# Main_DMB-4773.net
KiCad netlist of a schematic drawn in EAGLE
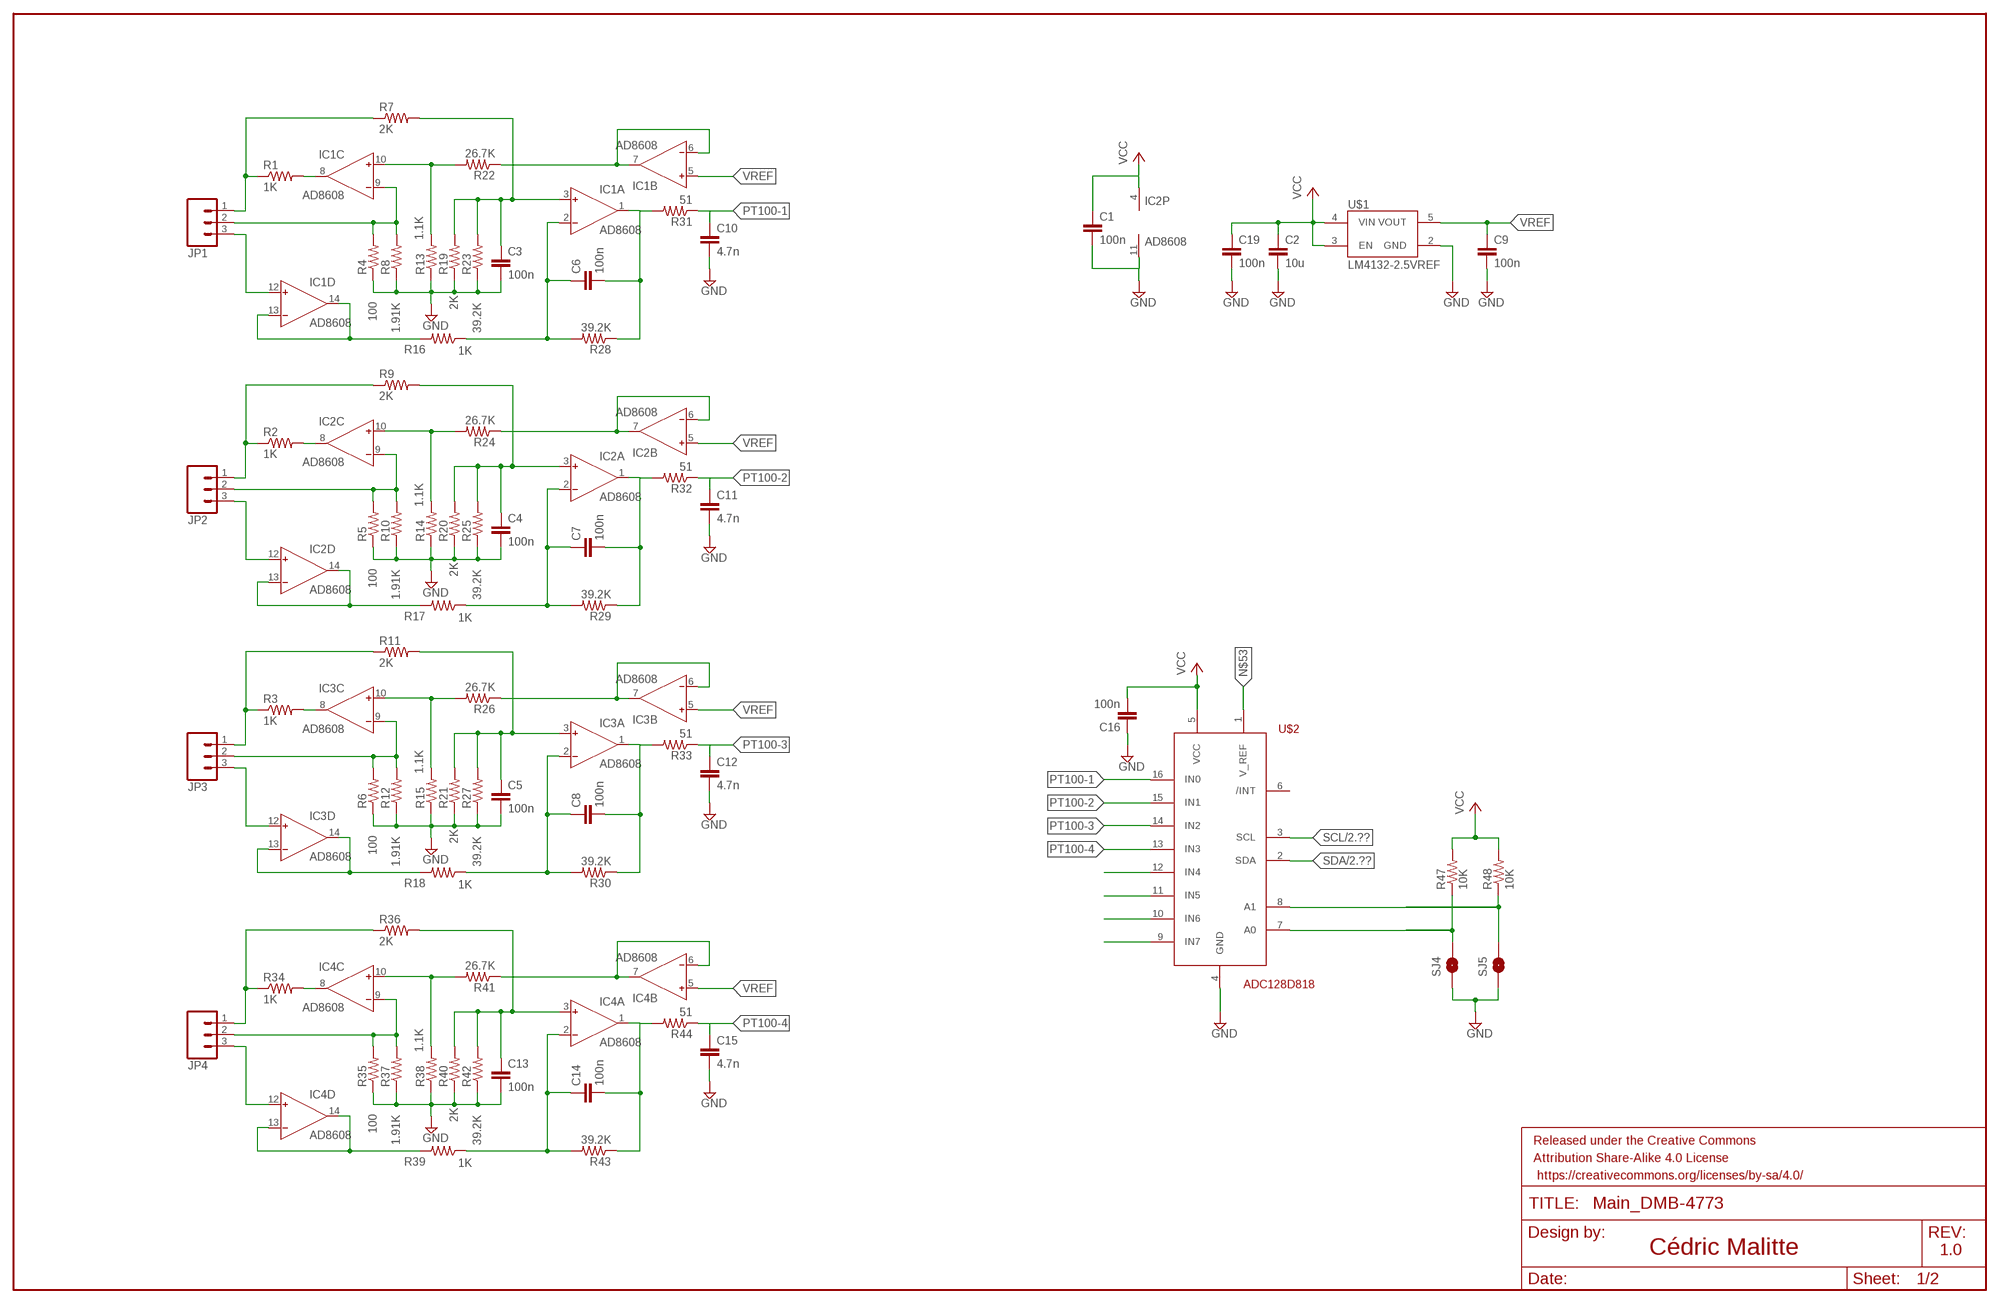
[diagram p0: schematic, sheet 1]
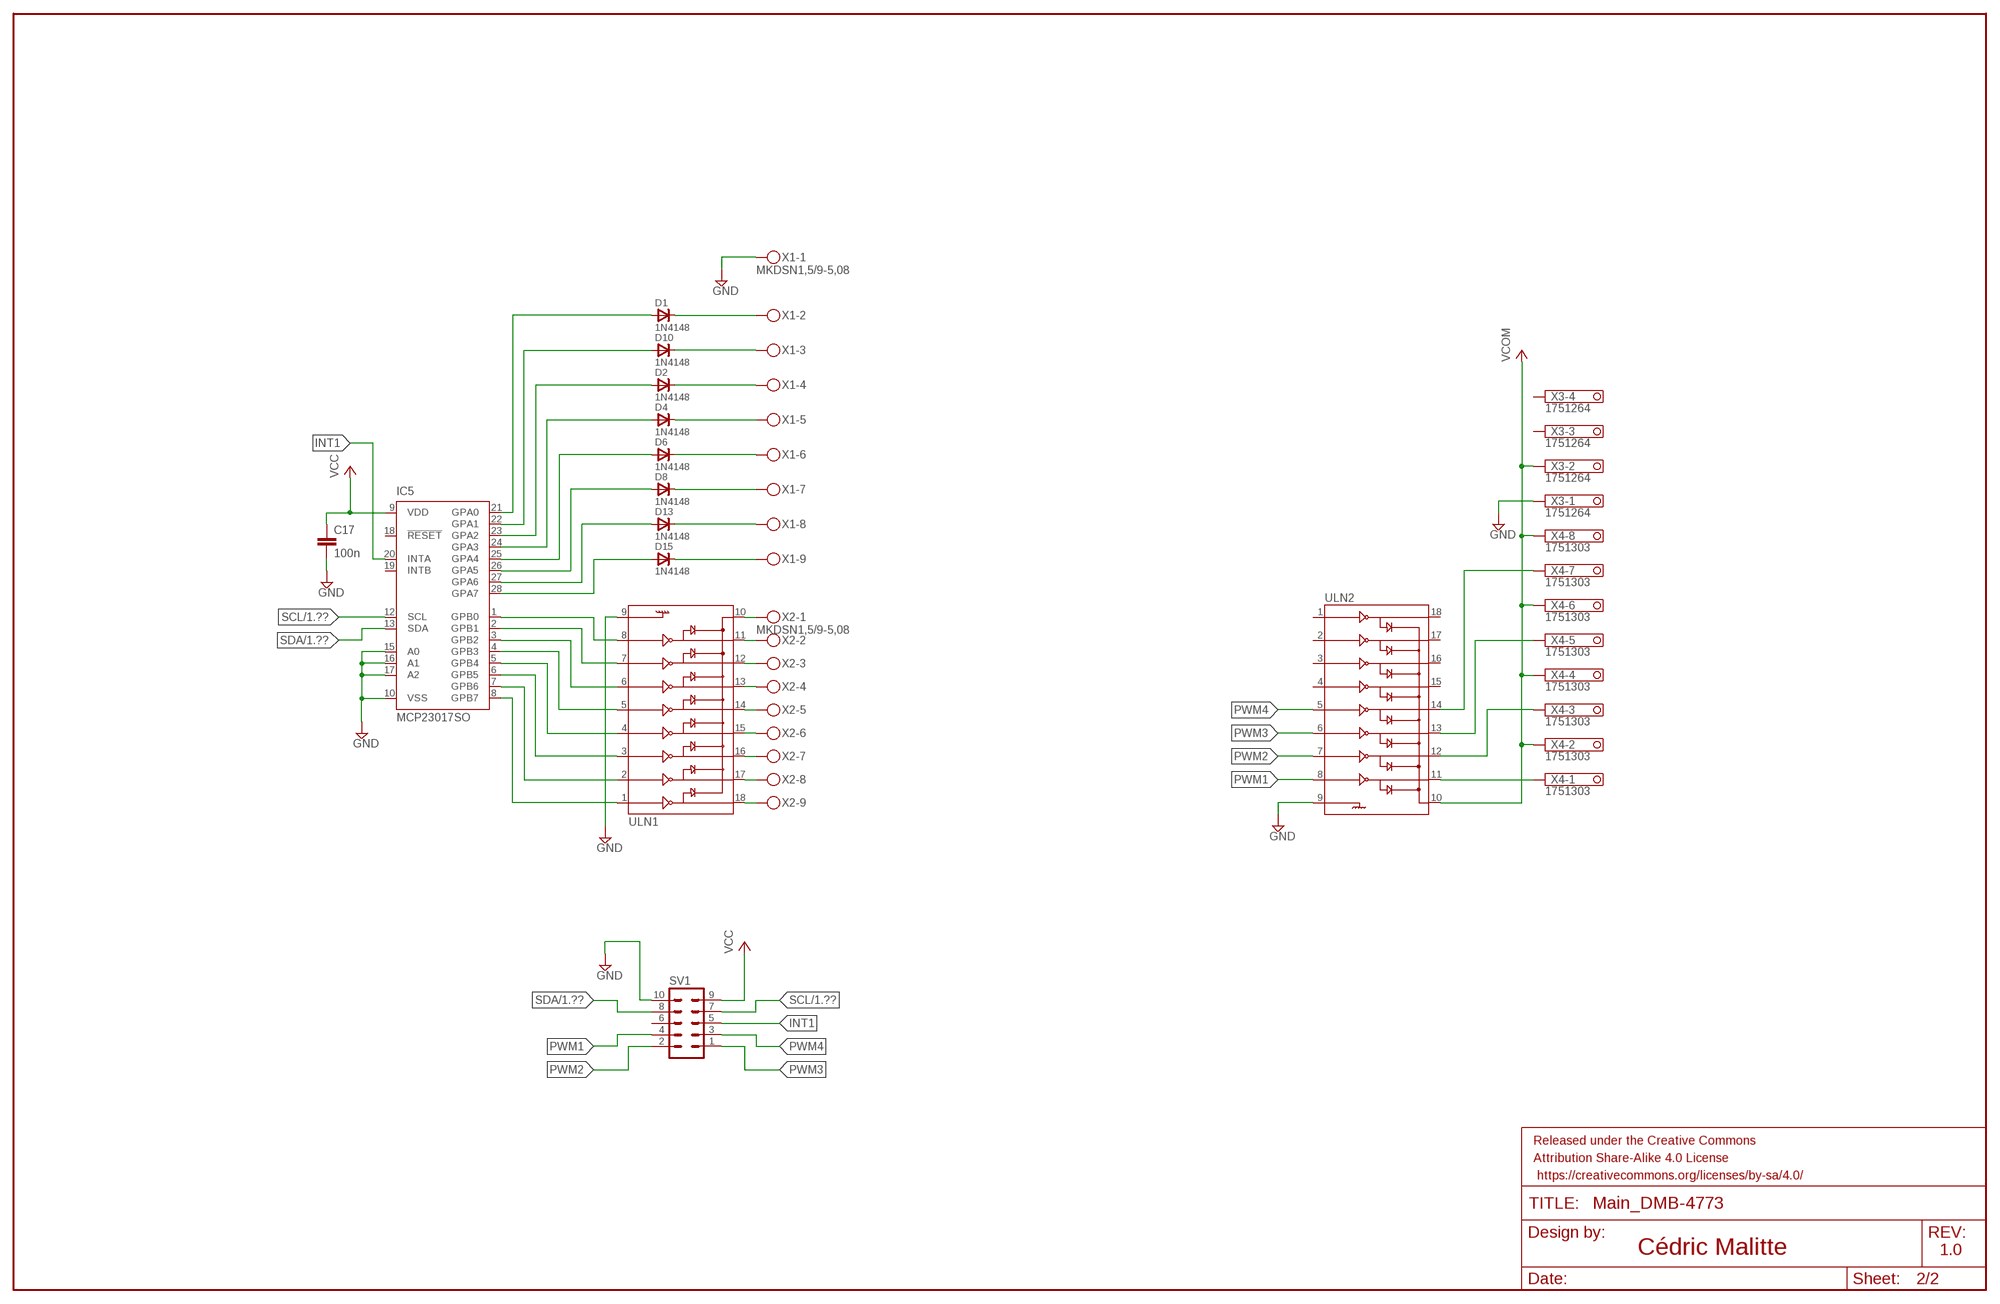
[diagram p1: schematic, sheet 2]

(export (version "E")
  (design (tool "Eeschema 10.0.6"))
  (components
    (comp (ref "C1")
      (value "100n")
      (footprint "eagle-import:0805")
      (libsource (lib "eagle-import") (part "CAP0805"))
    )
    (comp (ref "C2")
      (value "10u")
      (footprint "eagle-import:0805")
      (libsource (lib "eagle-import") (part "CAP0805"))
    )
    (comp (ref "C3")
      (value "100n")
      (footprint "eagle-import:0805")
      (libsource (lib "eagle-import") (part "CAP0805"))
    )
    (comp (ref "C4")
      (value "100n")
      (footprint "eagle-import:0805")
      (libsource (lib "eagle-import") (part "CAP0805"))
    )
    (comp (ref "C5")
      (value "100n")
      (footprint "eagle-import:0805")
      (libsource (lib "eagle-import") (part "CAP0805"))
    )
    (comp (ref "C6")
      (value "100n")
      (footprint "eagle-import:0805")
      (libsource (lib "eagle-import") (part "CAP0805"))
    )
    (comp (ref "C7")
      (value "100n")
      (footprint "eagle-import:0805")
      (libsource (lib "eagle-import") (part "CAP0805"))
    )
    (comp (ref "C8")
      (value "100n")
      (footprint "eagle-import:0805")
      (libsource (lib "eagle-import") (part "CAP0805"))
    )
    (comp (ref "C9")
      (value "100n")
      (footprint "eagle-import:0805")
      (libsource (lib "eagle-import") (part "CAP0805"))
    )
    (comp (ref "C10")
      (value "4.7n")
      (footprint "eagle-import:0805")
      (libsource (lib "eagle-import") (part "CAP0805"))
    )
    (comp (ref "C11")
      (value "4.7n")
      (footprint "eagle-import:0805")
      (libsource (lib "eagle-import") (part "CAP0805"))
    )
    (comp (ref "C12")
      (value "4.7n")
      (footprint "eagle-import:0805")
      (libsource (lib "eagle-import") (part "CAP0805"))
    )
    (comp (ref "C13")
      (value "100n")
      (footprint "eagle-import:0805")
      (libsource (lib "eagle-import") (part "CAP0805"))
    )
    (comp (ref "C14")
      (value "100n")
      (footprint "eagle-import:0805")
      (libsource (lib "eagle-import") (part "CAP0805"))
    )
    (comp (ref "C15")
      (value "4.7n")
      (footprint "eagle-import:0805")
      (libsource (lib "eagle-import") (part "CAP0805"))
    )
    (comp (ref "C16")
      (value "100n")
      (footprint "eagle-import:0805")
      (libsource (lib "eagle-import") (part "CAP0805"))
    )
    (comp (ref "C19")
      (value "100n")
      (footprint "eagle-import:0805")
      (libsource (lib "eagle-import") (part "CAP0805"))
    )
    (comp (ref "FRAME1")
      (value "FRAME-LEDGER")
      (footprint "eagle-import:CREATIVE_COMMONS")
      (libsource (lib "eagle-import") (part "FRAME-LEDGER"))
    )
    (comp (ref "IC1")
      (value "AD8608")
      (footprint "eagle-import:SO14")
      (fields (field (name "MPN") "AD8609ARZ"))
      (libsource (lib "eagle-import") (part "AD8609R"))
    )
    (comp (ref "IC2")
      (value "AD8608")
      (footprint "eagle-import:SO14")
      (fields (field (name "MPN") "AD8609ARZ"))
      (libsource (lib "eagle-import") (part "AD8609R"))
    )
    (comp (ref "IC3")
      (value "AD8608")
      (footprint "eagle-import:SO14")
      (fields (field (name "MPN") "AD8609ARZ"))
      (libsource (lib "eagle-import") (part "AD8609R"))
    )
    (comp (ref "IC4")
      (value "AD8608")
      (footprint "eagle-import:SO14")
      (fields (field (name "MPN") "AD8609ARZ"))
      (libsource (lib "eagle-import") (part "AD8609R"))
    )
    (comp (ref "JP1")
      (value "M03SCREW")
      (footprint "eagle-import:SCREWTERMINAL-3.5MM-3")
      (libsource (lib "eagle-import") (part "M03SCREW"))
    )
    (comp (ref "JP2")
      (value "M03SCREW")
      (footprint "eagle-import:SCREWTERMINAL-3.5MM-3")
      (libsource (lib "eagle-import") (part "M03SCREW"))
    )
    (comp (ref "JP3")
      (value "M03SCREW")
      (footprint "eagle-import:SCREWTERMINAL-3.5MM-3")
      (libsource (lib "eagle-import") (part "M03SCREW"))
    )
    (comp (ref "JP4")
      (value "M03SCREW")
      (footprint "eagle-import:SCREWTERMINAL-3.5MM-3")
      (libsource (lib "eagle-import") (part "M03SCREW"))
    )
    (comp (ref "R1")
      (value "1K")
      (footprint "eagle-import:0805")
      (libsource (lib "eagle-import") (part "RESISTOR0805-RES"))
    )
    (comp (ref "R2")
      (value "1K")
      (footprint "eagle-import:0805")
      (libsource (lib "eagle-import") (part "RESISTOR0805-RES"))
    )
    (comp (ref "R3")
      (value "1K")
      (footprint "eagle-import:0805")
      (libsource (lib "eagle-import") (part "RESISTOR0805-RES"))
    )
    (comp (ref "R4")
      (value "100")
      (footprint "eagle-import:0805")
      (libsource (lib "eagle-import") (part "RESISTOR0805-RES"))
    )
    (comp (ref "R5")
      (value "100")
      (footprint "eagle-import:0805")
      (libsource (lib "eagle-import") (part "RESISTOR0805-RES"))
    )
    (comp (ref "R6")
      (value "100")
      (footprint "eagle-import:0805")
      (libsource (lib "eagle-import") (part "RESISTOR0805-RES"))
    )
    (comp (ref "R7")
      (value "2K")
      (footprint "eagle-import:0805")
      (libsource (lib "eagle-import") (part "RESISTOR0805-RES"))
    )
    (comp (ref "R8")
      (value "1.91K")
      (footprint "eagle-import:0805")
      (libsource (lib "eagle-import") (part "RESISTOR0805-RES"))
    )
    (comp (ref "R9")
      (value "2K")
      (footprint "eagle-import:0805")
      (libsource (lib "eagle-import") (part "RESISTOR0805-RES"))
    )
    (comp (ref "R10")
      (value "1.91K")
      (footprint "eagle-import:0805")
      (libsource (lib "eagle-import") (part "RESISTOR0805-RES"))
    )
    (comp (ref "R11")
      (value "2K")
      (footprint "eagle-import:0805")
      (libsource (lib "eagle-import") (part "RESISTOR0805-RES"))
    )
    (comp (ref "R12")
      (value "1.91K")
      (footprint "eagle-import:0805")
      (libsource (lib "eagle-import") (part "RESISTOR0805-RES"))
    )
    (comp (ref "R13")
      (value "1.1K")
      (footprint "eagle-import:0805")
      (libsource (lib "eagle-import") (part "RESISTOR0805-RES"))
    )
    (comp (ref "R14")
      (value "1.1K")
      (footprint "eagle-import:0805")
      (libsource (lib "eagle-import") (part "RESISTOR0805-RES"))
    )
    (comp (ref "R15")
      (value "1.1K")
      (footprint "eagle-import:0805")
      (libsource (lib "eagle-import") (part "RESISTOR0805-RES"))
    )
    (comp (ref "R16")
      (value "1K")
      (footprint "eagle-import:0805")
      (libsource (lib "eagle-import") (part "RESISTOR0805-RES"))
    )
    (comp (ref "R17")
      (value "1K")
      (footprint "eagle-import:0805")
      (libsource (lib "eagle-import") (part "RESISTOR0805-RES"))
    )
    (comp (ref "R18")
      (value "1K")
      (footprint "eagle-import:0805")
      (libsource (lib "eagle-import") (part "RESISTOR0805-RES"))
    )
    (comp (ref "R19")
      (value "2K")
      (footprint "eagle-import:0805")
      (libsource (lib "eagle-import") (part "RESISTOR0805-RES"))
    )
    (comp (ref "R20")
      (value "2K")
      (footprint "eagle-import:0805")
      (libsource (lib "eagle-import") (part "RESISTOR0805-RES"))
    )
    (comp (ref "R21")
      (value "2K")
      (footprint "eagle-import:0805")
      (libsource (lib "eagle-import") (part "RESISTOR0805-RES"))
    )
    (comp (ref "R22")
      (value "26.7K")
      (footprint "eagle-import:0805")
      (libsource (lib "eagle-import") (part "RESISTOR0805-RES"))
    )
    (comp (ref "R23")
      (value "39.2K")
      (footprint "eagle-import:0805")
      (libsource (lib "eagle-import") (part "RESISTOR0805-RES"))
    )
    (comp (ref "R24")
      (value "26.7K")
      (footprint "eagle-import:0805")
      (libsource (lib "eagle-import") (part "RESISTOR0805-RES"))
    )
    (comp (ref "R25")
      (value "39.2K")
      (footprint "eagle-import:0805")
      (libsource (lib "eagle-import") (part "RESISTOR0805-RES"))
    )
    (comp (ref "R26")
      (value "26.7K")
      (footprint "eagle-import:0805")
      (libsource (lib "eagle-import") (part "RESISTOR0805-RES"))
    )
    (comp (ref "R27")
      (value "39.2K")
      (footprint "eagle-import:0805")
      (libsource (lib "eagle-import") (part "RESISTOR0805-RES"))
    )
    (comp (ref "R28")
      (value "39.2K")
      (footprint "eagle-import:0805")
      (libsource (lib "eagle-import") (part "RESISTOR0805-RES"))
    )
    (comp (ref "R29")
      (value "39.2K")
      (footprint "eagle-import:0805")
      (libsource (lib "eagle-import") (part "RESISTOR0805-RES"))
    )
    (comp (ref "R30")
      (value "39.2K")
      (footprint "eagle-import:0805")
      (libsource (lib "eagle-import") (part "RESISTOR0805-RES"))
    )
    (comp (ref "R31")
      (value "51")
      (footprint "eagle-import:0805")
      (libsource (lib "eagle-import") (part "RESISTOR0805-RES"))
    )
    (comp (ref "R32")
      (value "51")
      (footprint "eagle-import:0805")
      (libsource (lib "eagle-import") (part "RESISTOR0805-RES"))
    )
    (comp (ref "R33")
      (value "51")
      (footprint "eagle-import:0805")
      (libsource (lib "eagle-import") (part "RESISTOR0805-RES"))
    )
    (comp (ref "R34")
      (value "1K")
      (footprint "eagle-import:0805")
      (libsource (lib "eagle-import") (part "RESISTOR0805-RES"))
    )
    (comp (ref "R35")
      (value "100")
      (footprint "eagle-import:0805")
      (libsource (lib "eagle-import") (part "RESISTOR0805-RES"))
    )
    (comp (ref "R36")
      (value "2K")
      (footprint "eagle-import:0805")
      (libsource (lib "eagle-import") (part "RESISTOR0805-RES"))
    )
    (comp (ref "R37")
      (value "1.91K")
      (footprint "eagle-import:0805")
      (libsource (lib "eagle-import") (part "RESISTOR0805-RES"))
    )
    (comp (ref "R38")
      (value "1.1K")
      (footprint "eagle-import:0805")
      (libsource (lib "eagle-import") (part "RESISTOR0805-RES"))
    )
    (comp (ref "R39")
      (value "1K")
      (footprint "eagle-import:0805")
      (libsource (lib "eagle-import") (part "RESISTOR0805-RES"))
    )
    (comp (ref "R40")
      (value "2K")
      (footprint "eagle-import:0805")
      (libsource (lib "eagle-import") (part "RESISTOR0805-RES"))
    )
    (comp (ref "R41")
      (value "26.7K")
      (footprint "eagle-import:0805")
      (libsource (lib "eagle-import") (part "RESISTOR0805-RES"))
    )
    (comp (ref "R42")
      (value "39.2K")
      (footprint "eagle-import:0805")
      (libsource (lib "eagle-import") (part "RESISTOR0805-RES"))
    )
    (comp (ref "R43")
      (value "39.2K")
      (footprint "eagle-import:0805")
      (libsource (lib "eagle-import") (part "RESISTOR0805-RES"))
    )
    (comp (ref "R44")
      (value "51")
      (footprint "eagle-import:0805")
      (libsource (lib "eagle-import") (part "RESISTOR0805-RES"))
    )
    (comp (ref "R47")
      (value "10K")
      (footprint "eagle-import:0805")
      (libsource (lib "eagle-import") (part "RESISTOR0805-RES"))
    )
    (comp (ref "R48")
      (value "10K")
      (footprint "eagle-import:0805")
      (libsource (lib "eagle-import") (part "RESISTOR0805-RES"))
    )
    (comp (ref "SJ4")
      (value "SOLDERJUMPERNC")
      (footprint "eagle-import:SJ_2S")
      (libsource (lib "eagle-import") (part "SOLDERJUMPERNC"))
    )
    (comp (ref "SJ5")
      (value "SOLDERJUMPERNC")
      (footprint "eagle-import:SJ_2S")
      (libsource (lib "eagle-import") (part "SOLDERJUMPERNC"))
    )
    (comp (ref "U$1")
      (value "LM4132-2.5VREF")
      (footprint "eagle-import:SOT23-5")
      (libsource (lib "eagle-import") (part "LM4128-2.5VREF"))
    )
    (comp (ref "U$2")
      (value "ADC128D818")
      (footprint "eagle-import:SSOP16")
      (libsource (lib "eagle-import") (part "ADC128D818"))
    )
    (comp (ref "C17")
      (value "100n")
      (footprint "eagle-import:0805")
      (libsource (lib "eagle-import") (part "CAP0805"))
    )
    (comp (ref "D1")
      (value "1N4148")
      (footprint "eagle-import:DMINIMELF")
      (libsource (lib "eagle-import") (part "1N4148-MINIMELF"))
    )
    (comp (ref "D2")
      (value "1N4148")
      (footprint "eagle-import:DMINIMELF")
      (libsource (lib "eagle-import") (part "1N4148-MINIMELF"))
    )
    (comp (ref "D4")
      (value "1N4148")
      (footprint "eagle-import:DMINIMELF")
      (libsource (lib "eagle-import") (part "1N4148-MINIMELF"))
    )
    (comp (ref "D6")
      (value "1N4148")
      (footprint "eagle-import:DMINIMELF")
      (libsource (lib "eagle-import") (part "1N4148-MINIMELF"))
    )
    (comp (ref "D8")
      (value "1N4148")
      (footprint "eagle-import:DMINIMELF")
      (libsource (lib "eagle-import") (part "1N4148-MINIMELF"))
    )
    (comp (ref "D10")
      (value "1N4148")
      (footprint "eagle-import:DMINIMELF")
      (libsource (lib "eagle-import") (part "1N4148-MINIMELF"))
    )
    (comp (ref "D13")
      (value "1N4148")
      (footprint "eagle-import:DMINIMELF")
      (libsource (lib "eagle-import") (part "1N4148-MINIMELF"))
    )
    (comp (ref "D15")
      (value "1N4148")
      (footprint "eagle-import:DMINIMELF")
      (libsource (lib "eagle-import") (part "1N4148-MINIMELF"))
    )
    (comp (ref "FRAME2")
      (value "FRAME-LEDGER")
      (footprint "eagle-import:CREATIVE_COMMONS")
      (libsource (lib "eagle-import") (part "FRAME-LEDGER"))
    )
    (comp (ref "IC5")
      (value "MCP23017SO")
      (footprint "eagle-import:SO28W")
      (fields (field (name "MF") "MICROCHIP") (field (name "MPN") "MCP23017-E/SO"))
      (libsource (lib "eagle-import") (part "MCP23017SO"))
    )
    (comp (ref "SV1")
      (value "ML10")
      (footprint "eagle-import:ML10")
      (libsource (lib "eagle-import") (part "ML10"))
    )
    (comp (ref "ULN1")
      (value "ULN2803SOIC")
      (footprint "eagle-import:SO018")
      (libsource (lib "eagle-import") (part "ULN2803SOIC"))
    )
    (comp (ref "ULN2")
      (value "ULN2803SOIC")
      (footprint "eagle-import:SO018")
      (libsource (lib "eagle-import") (part "ULN2803SOIC"))
    )
    (comp (ref "X1")
      (value "MKDSN1,5/9-5,08")
      (footprint "eagle-import:MKDSN1,5_9-5,08")
      (fields (field (name "MPN") "SMKDSN1,5/9-5,08"))
      (libsource (lib "eagle-import") (part "MKDSN1,5/9-5,08"))
    )
    (comp (ref "X2")
      (value "MKDSN1,5/9-5,08")
      (footprint "eagle-import:MKDSN1,5_9-5,08")
      (fields (field (name "MPN") "SMKDSN1,5/9-5,08"))
      (libsource (lib "eagle-import") (part "MKDSN1,5/9-5,08"))
    )
    (comp (ref "X3")
      (value "1751264")
      (footprint "eagle-import:1751264")
      (libsource (lib "eagle-import") (part "1751264"))
    )
    (comp (ref "X4")
      (value "1751303")
      (footprint "eagle-import:1751303")
      (libsource (lib "eagle-import") (part "1751303"))
    )
  )
  (nets
    (net (code "1") (name "GND") (class "Default")
      (node (ref "C1") (pin "2") (pinfunction "2_2") (pintype "passive"))
      (node (ref "C10") (pin "2") (pinfunction "2_2") (pintype "passive"))
      (node (ref "C11") (pin "2") (pinfunction "2_2") (pintype "passive"))
      (node (ref "C12") (pin "2") (pinfunction "2_2") (pintype "passive"))
      (node (ref "C13") (pin "2") (pinfunction "2_2") (pintype "passive"))
      (node (ref "C15") (pin "2") (pinfunction "2_2") (pintype "passive"))
      (node (ref "C16") (pin "1") (pinfunction "1_1") (pintype "passive"))
      (node (ref "C17") (pin "2") (pinfunction "2_2") (pintype "passive"))
      (node (ref "C19") (pin "2") (pinfunction "2_2") (pintype "passive"))
      (node (ref "C2") (pin "2") (pinfunction "2_2") (pintype "passive"))
      (node (ref "C3") (pin "2") (pinfunction "2_2") (pintype "passive"))
      (node (ref "C4") (pin "2") (pinfunction "2_2") (pintype "passive"))
      (node (ref "C5") (pin "2") (pinfunction "2_2") (pintype "passive"))
      (node (ref "C9") (pin "2") (pinfunction "2_2") (pintype "passive"))
      (node (ref "IC2") (pin "11") (pinfunction "V-_11") (pintype "power_in"))
      (node (ref "IC5") (pin "10") (pinfunction "VSS_10") (pintype "power_in"))
      (node (ref "IC5") (pin "15") (pinfunction "A0_15") (pintype "input"))
      (node (ref "IC5") (pin "16") (pinfunction "A1_16") (pintype "input"))
      (node (ref "IC5") (pin "17") (pinfunction "A2_17") (pintype "input"))
      (node (ref "R10") (pin "1") (pinfunction "1_1") (pintype "passive"))
      (node (ref "R12") (pin "1") (pinfunction "1_1") (pintype "passive"))
      (node (ref "R13") (pin "1") (pinfunction "1_1") (pintype "passive"))
      (node (ref "R14") (pin "1") (pinfunction "1_1") (pintype "passive"))
      (node (ref "R15") (pin "1") (pinfunction "1_1") (pintype "passive"))
      (node (ref "R19") (pin "1") (pinfunction "1_1") (pintype "passive"))
      (node (ref "R20") (pin "1") (pinfunction "1_1") (pintype "passive"))
      (node (ref "R21") (pin "1") (pinfunction "1_1") (pintype "passive"))
      (node (ref "R23") (pin "1") (pinfunction "1_1") (pintype "passive"))
      (node (ref "R25") (pin "1") (pinfunction "1_1") (pintype "passive"))
      (node (ref "R27") (pin "1") (pinfunction "1_1") (pintype "passive"))
      (node (ref "R35") (pin "1") (pinfunction "1_1") (pintype "passive"))
      (node (ref "R37") (pin "1") (pinfunction "1_1") (pintype "passive"))
      (node (ref "R38") (pin "1") (pinfunction "1_1") (pintype "passive"))
      (node (ref "R4") (pin "1") (pinfunction "1_1") (pintype "passive"))
      (node (ref "R40") (pin "1") (pinfunction "1_1") (pintype "passive"))
      (node (ref "R42") (pin "1") (pinfunction "1_1") (pintype "passive"))
      (node (ref "R5") (pin "1") (pinfunction "1_1") (pintype "passive"))
      (node (ref "R6") (pin "1") (pinfunction "1_1") (pintype "passive"))
      (node (ref "R8") (pin "1") (pinfunction "1_1") (pintype "passive"))
      (node (ref "SJ4") (pin "1") (pinfunction "1_1") (pintype "passive"))
      (node (ref "SJ5") (pin "1") (pinfunction "1_1") (pintype "passive"))
      (node (ref "SV1") (pin "10") (pinfunction "10_10") (pintype "passive"))
      (node (ref "U$1") (pin "2") (pinfunction "GND_2") (pintype "bidirectional"))
      (node (ref "U$2") (pin "4") (pinfunction "GND_4") (pintype "power_in"))
      (node (ref "ULN1") (pin "9") (pinfunction "9_9") (pintype "bidirectional"))
      (node (ref "ULN2") (pin "9") (pinfunction "9_9") (pintype "bidirectional"))
      (node (ref "X1") (pin "1") (pinfunction "KL_1") (pintype "passive"))
      (node (ref "X3") (pin "1") (pinfunction "K_1") (pintype "passive"))
    )
    (net (code "2") (name "INT1") (class "Default")
      (node (ref "IC5") (pin "20") (pinfunction "INTA_20") (pintype "output"))
      (node (ref "SV1") (pin "5") (pinfunction "5_5") (pintype "passive"))
    )
    (net (code "3") (name "N$53") (class "Default")
      (node (ref "U$2") (pin "1") (pinfunction "V_REF_1") (pintype "input"))
    )
    (net (code "4") (name "Net-(IC1A-IN+)") (class "Default")
      (node (ref "C3") (pin "1") (pinfunction "1_1") (pintype "passive"))
      (node (ref "IC1") (pin "3") (pinfunction "IN+_3") (pintype "input"))
      (node (ref "R19") (pin "2") (pinfunction "2_2") (pintype "passive"))
      (node (ref "R23") (pin "2") (pinfunction "2_2") (pintype "passive"))
      (node (ref "R7") (pin "2") (pinfunction "2_2") (pintype "passive"))
    )
    (net (code "5") (name "Net-(IC1A-IN-)") (class "Default")
      (node (ref "C6") (pin "1") (pinfunction "1_1") (pintype "passive"))
      (node (ref "IC1") (pin "2") (pinfunction "IN-_2") (pintype "input"))
      (node (ref "R16") (pin "1") (pinfunction "1_1") (pintype "passive"))
      (node (ref "R28") (pin "2") (pinfunction "2_2") (pintype "passive"))
    )
    (net (code "6") (name "Net-(IC1A-OUT)") (class "Default")
      (node (ref "C6") (pin "2") (pinfunction "2_2") (pintype "passive"))
      (node (ref "IC1") (pin "1") (pinfunction "OUT_1") (pintype "output"))
      (node (ref "R28") (pin "1") (pinfunction "1_1") (pintype "passive"))
      (node (ref "R31") (pin "2") (pinfunction "2_2") (pintype "passive"))
    )
    (net (code "7") (name "Net-(IC1B-IN-)") (class "Default")
      (node (ref "IC1") (pin "6") (pinfunction "IN-_6") (pintype "input"))
      (node (ref "IC1") (pin "7") (pinfunction "OUT_7") (pintype "output"))
      (node (ref "R22") (pin "1") (pinfunction "1_1") (pintype "passive"))
    )
    (net (code "8") (name "Net-(IC1C-IN+)") (class "Default")
      (node (ref "IC1") (pin "10") (pinfunction "IN+_10") (pintype "input"))
      (node (ref "R13") (pin "2") (pinfunction "2_2") (pintype "passive"))
      (node (ref "R22") (pin "2") (pinfunction "2_2") (pintype "passive"))
    )
    (net (code "9") (name "Net-(IC1C-IN-)") (class "Default")
      (node (ref "IC1") (pin "9") (pinfunction "IN-_9") (pintype "input"))
      (node (ref "JP1") (pin "2") (pinfunction "2_2") (pintype "passive"))
      (node (ref "R4") (pin "2") (pinfunction "2_2") (pintype "passive"))
      (node (ref "R8") (pin "2") (pinfunction "2_2") (pintype "passive"))
    )
    (net (code "10") (name "Net-(IC1C-OUT)") (class "Default")
      (node (ref "IC1") (pin "8") (pinfunction "OUT_8") (pintype "output"))
      (node (ref "R1") (pin "2") (pinfunction "2_2") (pintype "passive"))
    )
    (net (code "11") (name "Net-(IC1D-IN+)") (class "Default")
      (node (ref "IC1") (pin "12") (pinfunction "IN+_12") (pintype "input"))
      (node (ref "JP1") (pin "3") (pinfunction "3_3") (pintype "passive"))
    )
    (net (code "12") (name "Net-(IC1D-IN-)") (class "Default")
      (node (ref "IC1") (pin "13") (pinfunction "IN-_13") (pintype "input"))
      (node (ref "IC1") (pin "14") (pinfunction "OUT_14") (pintype "output"))
      (node (ref "R16") (pin "2") (pinfunction "2_2") (pintype "passive"))
    )
    (net (code "13") (name "Net-(IC2A-IN+)") (class "Default")
      (node (ref "C4") (pin "1") (pinfunction "1_1") (pintype "passive"))
      (node (ref "IC2") (pin "3") (pinfunction "IN+_3") (pintype "input"))
      (node (ref "R20") (pin "2") (pinfunction "2_2") (pintype "passive"))
      (node (ref "R25") (pin "2") (pinfunction "2_2") (pintype "passive"))
      (node (ref "R9") (pin "2") (pinfunction "2_2") (pintype "passive"))
    )
    (net (code "14") (name "Net-(IC2A-IN-)") (class "Default")
      (node (ref "C7") (pin "1") (pinfunction "1_1") (pintype "passive"))
      (node (ref "IC2") (pin "2") (pinfunction "IN-_2") (pintype "input"))
      (node (ref "R17") (pin "1") (pinfunction "1_1") (pintype "passive"))
      (node (ref "R29") (pin "2") (pinfunction "2_2") (pintype "passive"))
    )
    (net (code "15") (name "Net-(IC2A-OUT)") (class "Default")
      (node (ref "C7") (pin "2") (pinfunction "2_2") (pintype "passive"))
      (node (ref "IC2") (pin "1") (pinfunction "OUT_1") (pintype "output"))
      (node (ref "R29") (pin "1") (pinfunction "1_1") (pintype "passive"))
      (node (ref "R32") (pin "2") (pinfunction "2_2") (pintype "passive"))
    )
    (net (code "16") (name "Net-(IC2B-IN-)") (class "Default")
      (node (ref "IC2") (pin "6") (pinfunction "IN-_6") (pintype "input"))
      (node (ref "IC2") (pin "7") (pinfunction "OUT_7") (pintype "output"))
      (node (ref "R24") (pin "1") (pinfunction "1_1") (pintype "passive"))
    )
    (net (code "17") (name "Net-(IC2C-IN+)") (class "Default")
      (node (ref "IC2") (pin "10") (pinfunction "IN+_10") (pintype "input"))
      (node (ref "R14") (pin "2") (pinfunction "2_2") (pintype "passive"))
      (node (ref "R24") (pin "2") (pinfunction "2_2") (pintype "passive"))
    )
    (net (code "18") (name "Net-(IC2C-IN-)") (class "Default")
      (node (ref "IC2") (pin "9") (pinfunction "IN-_9") (pintype "input"))
      (node (ref "JP2") (pin "2") (pinfunction "2_2") (pintype "passive"))
      (node (ref "R10") (pin "2") (pinfunction "2_2") (pintype "passive"))
      (node (ref "R5") (pin "2") (pinfunction "2_2") (pintype "passive"))
    )
    (net (code "19") (name "Net-(IC2C-OUT)") (class "Default")
      (node (ref "IC2") (pin "8") (pinfunction "OUT_8") (pintype "output"))
      (node (ref "R2") (pin "2") (pinfunction "2_2") (pintype "passive"))
    )
    (net (code "20") (name "Net-(IC2D-IN+)") (class "Default")
      (node (ref "IC2") (pin "12") (pinfunction "IN+_12") (pintype "input"))
      (node (ref "JP2") (pin "3") (pinfunction "3_3") (pintype "passive"))
    )
    (net (code "21") (name "Net-(IC2D-IN-)") (class "Default")
      (node (ref "IC2") (pin "13") (pinfunction "IN-_13") (pintype "input"))
      (node (ref "IC2") (pin "14") (pinfunction "OUT_14") (pintype "output"))
      (node (ref "R17") (pin "2") (pinfunction "2_2") (pintype "passive"))
    )
    (net (code "22") (name "Net-(IC3A-IN+)") (class "Default")
      (node (ref "C5") (pin "1") (pinfunction "1_1") (pintype "passive"))
      (node (ref "IC3") (pin "3") (pinfunction "IN+_3") (pintype "input"))
      (node (ref "R11") (pin "2") (pinfunction "2_2") (pintype "passive"))
      (node (ref "R21") (pin "2") (pinfunction "2_2") (pintype "passive"))
      (node (ref "R27") (pin "2") (pinfunction "2_2") (pintype "passive"))
    )
    (net (code "23") (name "Net-(IC3A-IN-)") (class "Default")
      (node (ref "C8") (pin "1") (pinfunction "1_1") (pintype "passive"))
      (node (ref "IC3") (pin "2") (pinfunction "IN-_2") (pintype "input"))
      (node (ref "R18") (pin "1") (pinfunction "1_1") (pintype "passive"))
      (node (ref "R30") (pin "2") (pinfunction "2_2") (pintype "passive"))
    )
    (net (code "24") (name "Net-(IC3A-OUT)") (class "Default")
      (node (ref "C8") (pin "2") (pinfunction "2_2") (pintype "passive"))
      (node (ref "IC3") (pin "1") (pinfunction "OUT_1") (pintype "output"))
      (node (ref "R30") (pin "1") (pinfunction "1_1") (pintype "passive"))
      (node (ref "R33") (pin "2") (pinfunction "2_2") (pintype "passive"))
    )
    (net (code "25") (name "Net-(IC3B-IN-)") (class "Default")
      (node (ref "IC3") (pin "6") (pinfunction "IN-_6") (pintype "input"))
      (node (ref "IC3") (pin "7") (pinfunction "OUT_7") (pintype "output"))
      (node (ref "R26") (pin "1") (pinfunction "1_1") (pintype "passive"))
    )
    (net (code "26") (name "Net-(IC3C-IN+)") (class "Default")
      (node (ref "IC3") (pin "10") (pinfunction "IN+_10") (pintype "input"))
      (node (ref "R15") (pin "2") (pinfunction "2_2") (pintype "passive"))
      (node (ref "R26") (pin "2") (pinfunction "2_2") (pintype "passive"))
    )
    (net (code "27") (name "Net-(IC3C-IN-)") (class "Default")
      (node (ref "IC3") (pin "9") (pinfunction "IN-_9") (pintype "input"))
      (node (ref "JP3") (pin "2") (pinfunction "2_2") (pintype "passive"))
      (node (ref "R12") (pin "2") (pinfunction "2_2") (pintype "passive"))
      (node (ref "R6") (pin "2") (pinfunction "2_2") (pintype "passive"))
    )
    (net (code "28") (name "Net-(IC3C-OUT)") (class "Default")
      (node (ref "IC3") (pin "8") (pinfunction "OUT_8") (pintype "output"))
      (node (ref "R3") (pin "2") (pinfunction "2_2") (pintype "passive"))
    )
    (net (code "29") (name "Net-(IC3D-IN+)") (class "Default")
      (node (ref "IC3") (pin "12") (pinfunction "IN+_12") (pintype "input"))
      (node (ref "JP3") (pin "3") (pinfunction "3_3") (pintype "passive"))
    )
    (net (code "30") (name "Net-(IC3D-IN-)") (class "Default")
      (node (ref "IC3") (pin "13") (pinfunction "IN-_13") (pintype "input"))
      (node (ref "IC3") (pin "14") (pinfunction "OUT_14") (pintype "output"))
      (node (ref "R18") (pin "2") (pinfunction "2_2") (pintype "passive"))
    )
    (net (code "31") (name "Net-(IC4A-IN+)") (class "Default")
      (node (ref "C13") (pin "1") (pinfunction "1_1") (pintype "passive"))
      (node (ref "IC4") (pin "3") (pinfunction "IN+_3") (pintype "input"))
      (node (ref "R36") (pin "2") (pinfunction "2_2") (pintype "passive"))
      (node (ref "R40") (pin "2") (pinfunction "2_2") (pintype "passive"))
      (node (ref "R42") (pin "2") (pinfunction "2_2") (pintype "passive"))
    )
    (net (code "32") (name "Net-(IC4A-IN-)") (class "Default")
      (node (ref "C14") (pin "1") (pinfunction "1_1") (pintype "passive"))
      (node (ref "IC4") (pin "2") (pinfunction "IN-_2") (pintype "input"))
      (node (ref "R39") (pin "1") (pinfunction "1_1") (pintype "passive"))
      (node (ref "R43") (pin "2") (pinfunction "2_2") (pintype "passive"))
    )
    (net (code "33") (name "Net-(IC4A-OUT)") (class "Default")
      (node (ref "C14") (pin "2") (pinfunction "2_2") (pintype "passive"))
      (node (ref "IC4") (pin "1") (pinfunction "OUT_1") (pintype "output"))
      (node (ref "R43") (pin "1") (pinfunction "1_1") (pintype "passive"))
      (node (ref "R44") (pin "2") (pinfunction "2_2") (pintype "passive"))
    )
    (net (code "34") (name "Net-(IC4B-IN-)") (class "Default")
      (node (ref "IC4") (pin "6") (pinfunction "IN-_6") (pintype "input"))
      (node (ref "IC4") (pin "7") (pinfunction "OUT_7") (pintype "output"))
      (node (ref "R41") (pin "1") (pinfunction "1_1") (pintype "passive"))
    )
    (net (code "35") (name "Net-(IC4C-IN+)") (class "Default")
      (node (ref "IC4") (pin "10") (pinfunction "IN+_10") (pintype "input"))
      (node (ref "R38") (pin "2") (pinfunction "2_2") (pintype "passive"))
      (node (ref "R41") (pin "2") (pinfunction "2_2") (pintype "passive"))
    )
    (net (code "36") (name "Net-(IC4C-IN-)") (class "Default")
      (node (ref "IC4") (pin "9") (pinfunction "IN-_9") (pintype "input"))
      (node (ref "JP4") (pin "2") (pinfunction "2_2") (pintype "passive"))
      (node (ref "R35") (pin "2") (pinfunction "2_2") (pintype "passive"))
      (node (ref "R37") (pin "2") (pinfunction "2_2") (pintype "passive"))
    )
    (net (code "37") (name "Net-(IC4C-OUT)") (class "Default")
      (node (ref "IC4") (pin "8") (pinfunction "OUT_8") (pintype "output"))
      (node (ref "R34") (pin "2") (pinfunction "2_2") (pintype "passive"))
    )
    (net (code "38") (name "Net-(IC4D-IN+)") (class "Default")
      (node (ref "IC4") (pin "12") (pinfunction "IN+_12") (pintype "input"))
      (node (ref "JP4") (pin "3") (pinfunction "3_3") (pintype "passive"))
    )
    (net (code "39") (name "Net-(IC4D-IN-)") (class "Default")
      (node (ref "IC4") (pin "13") (pinfunction "IN-_13") (pintype "input"))
      (node (ref "IC4") (pin "14") (pinfunction "OUT_14") (pintype "output"))
      (node (ref "R39") (pin "2") (pinfunction "2_2") (pintype "passive"))
    )
    (net (code "40") (name "Net-(IC5-GPA0)") (class "Default")
      (node (ref "D1") (pin "A") (pinfunction "A_A") (pintype "passive"))
      (node (ref "IC5") (pin "21") (pinfunction "GPA0_21") (pintype "bidirectional"))
    )
    (net (code "41") (name "Net-(IC5-GPA1)") (class "Default")
      (node (ref "D10") (pin "A") (pinfunction "A_A") (pintype "passive"))
      (node (ref "IC5") (pin "22") (pinfunction "GPA1_22") (pintype "bidirectional"))
    )
    (net (code "42") (name "Net-(IC5-GPA2)") (class "Default")
      (node (ref "D2") (pin "A") (pinfunction "A_A") (pintype "passive"))
      (node (ref "IC5") (pin "23") (pinfunction "GPA2_23") (pintype "bidirectional"))
    )
    (net (code "43") (name "Net-(IC5-GPA3)") (class "Default")
      (node (ref "D4") (pin "A") (pinfunction "A_A") (pintype "passive"))
      (node (ref "IC5") (pin "24") (pinfunction "GPA3_24") (pintype "bidirectional"))
    )
    (net (code "44") (name "Net-(IC5-GPA4)") (class "Default")
      (node (ref "D6") (pin "A") (pinfunction "A_A") (pintype "passive"))
      (node (ref "IC5") (pin "25") (pinfunction "GPA4_25") (pintype "bidirectional"))
    )
    (net (code "45") (name "Net-(IC5-GPA5)") (class "Default")
      (node (ref "D8") (pin "A") (pinfunction "A_A") (pintype "passive"))
      (node (ref "IC5") (pin "26") (pinfunction "GPA5_26") (pintype "bidirectional"))
    )
    (net (code "46") (name "Net-(IC5-GPA6)") (class "Default")
      (node (ref "D13") (pin "A") (pinfunction "A_A") (pintype "passive"))
      (node (ref "IC5") (pin "27") (pinfunction "GPA6_27") (pintype "bidirectional"))
    )
    (net (code "47") (name "Net-(IC5-GPA7)") (class "Default")
      (node (ref "D15") (pin "A") (pinfunction "A_A") (pintype "passive"))
      (node (ref "IC5") (pin "28") (pinfunction "GPA7_28") (pintype "bidirectional"))
    )
    (net (code "48") (name "Net-(IC5-GPB0)") (class "Default")
      (node (ref "IC5") (pin "1") (pinfunction "GPB0_1") (pintype "bidirectional"))
      (node (ref "ULN1") (pin "8") (pinfunction "8_8") (pintype "bidirectional"))
    )
    (net (code "49") (name "Net-(IC5-GPB1)") (class "Default")
      (node (ref "IC5") (pin "2") (pinfunction "GPB1_2") (pintype "bidirectional"))
      (node (ref "ULN1") (pin "7") (pinfunction "7_7") (pintype "bidirectional"))
    )
    (net (code "50") (name "Net-(IC5-GPB2)") (class "Default")
      (node (ref "IC5") (pin "3") (pinfunction "GPB2_3") (pintype "bidirectional"))
      (node (ref "ULN1") (pin "6") (pinfunction "6_6") (pintype "bidirectional"))
    )
    (net (code "51") (name "Net-(IC5-GPB3)") (class "Default")
      (node (ref "IC5") (pin "4") (pinfunction "GPB3_4") (pintype "bidirectional"))
      (node (ref "ULN1") (pin "5") (pinfunction "5_5") (pintype "bidirectional"))
    )
    (net (code "52") (name "Net-(IC5-GPB4)") (class "Default")
      (node (ref "IC5") (pin "5") (pinfunction "GPB4_5") (pintype "bidirectional"))
      (node (ref "ULN1") (pin "4") (pinfunction "4_4") (pintype "bidirectional"))
    )
    (net (code "53") (name "Net-(IC5-GPB5)") (class "Default")
      (node (ref "IC5") (pin "6") (pinfunction "GPB5_6") (pintype "bidirectional"))
      (node (ref "ULN1") (pin "3") (pinfunction "3_3") (pintype "bidirectional"))
    )
    (net (code "54") (name "Net-(IC5-GPB6)") (class "Default")
      (node (ref "IC5") (pin "7") (pinfunction "GPB6_7") (pintype "bidirectional"))
      (node (ref "ULN1") (pin "2") (pinfunction "2_2") (pintype "bidirectional"))
    )
    (net (code "55") (name "Net-(IC5-GPB7)") (class "Default")
      (node (ref "IC5") (pin "8") (pinfunction "GPB7_8") (pintype "bidirectional"))
      (node (ref "ULN1") (pin "1") (pinfunction "1_1") (pintype "bidirectional"))
    )
    (net (code "56") (name "Net-(JP1-Pad1)") (class "Default")
      (node (ref "JP1") (pin "1") (pinfunction "1_1") (pintype "passive"))
      (node (ref "R1") (pin "1") (pinfunction "1_1") (pintype "passive"))
      (node (ref "R7") (pin "1") (pinfunction "1_1") (pintype "passive"))
    )
    (net (code "57") (name "Net-(JP2-Pad1)") (class "Default")
      (node (ref "JP2") (pin "1") (pinfunction "1_1") (pintype "passive"))
      (node (ref "R2") (pin "1") (pinfunction "1_1") (pintype "passive"))
      (node (ref "R9") (pin "1") (pinfunction "1_1") (pintype "passive"))
    )
    (net (code "58") (name "Net-(JP3-Pad1)") (class "Default")
      (node (ref "JP3") (pin "1") (pinfunction "1_1") (pintype "passive"))
      (node (ref "R11") (pin "1") (pinfunction "1_1") (pintype "passive"))
      (node (ref "R3") (pin "1") (pinfunction "1_1") (pintype "passive"))
    )
    (net (code "59") (name "Net-(JP4-Pad1)") (class "Default")
      (node (ref "JP4") (pin "1") (pinfunction "1_1") (pintype "passive"))
      (node (ref "R34") (pin "1") (pinfunction "1_1") (pintype "passive"))
      (node (ref "R36") (pin "1") (pinfunction "1_1") (pintype "passive"))
    )
    (net (code "60") (name "Net-(U$2-A0)") (class "Default")
      (node (ref "R47") (pin "1") (pinfunction "1_1") (pintype "passive"))
      (node (ref "SJ4") (pin "2") (pinfunction "2_2") (pintype "passive"))
      (node (ref "U$2") (pin "7") (pinfunction "A0_7") (pintype "input"))
    )
    (net (code "61") (name "Net-(U$2-A1)") (class "Default")
      (node (ref "R48") (pin "1") (pinfunction "1_1") (pintype "passive"))
      (node (ref "SJ5") (pin "2") (pinfunction "2_2") (pintype "passive"))
      (node (ref "U$2") (pin "8") (pinfunction "A1_8") (pintype "input"))
    )
    (net (code "62") (name "Net-(X1B-KL)") (class "Default")
      (node (ref "D1") (pin "C") (pinfunction "C_C") (pintype "passive"))
      (node (ref "X1") (pin "2") (pinfunction "KL_2") (pintype "passive"))
    )
    (net (code "63") (name "Net-(X1C-KL)") (class "Default")
      (node (ref "D10") (pin "C") (pinfunction "C_C") (pintype "passive"))
      (node (ref "X1") (pin "3") (pinfunction "KL_3") (pintype "passive"))
    )
    (net (code "64") (name "Net-(X1D-KL)") (class "Default")
      (node (ref "D2") (pin "C") (pinfunction "C_C") (pintype "passive"))
      (node (ref "X1") (pin "4") (pinfunction "KL_4") (pintype "passive"))
    )
    (net (code "65") (name "Net-(X1E-KL)") (class "Default")
      (node (ref "D4") (pin "C") (pinfunction "C_C") (pintype "passive"))
      (node (ref "X1") (pin "5") (pinfunction "KL_5") (pintype "passive"))
    )
    (net (code "66") (name "Net-(X1F-KL)") (class "Default")
      (node (ref "D6") (pin "C") (pinfunction "C_C") (pintype "passive"))
      (node (ref "X1") (pin "6") (pinfunction "KL_6") (pintype "passive"))
    )
    (net (code "67") (name "Net-(X1G-KL)") (class "Default")
      (node (ref "D8") (pin "C") (pinfunction "C_C") (pintype "passive"))
      (node (ref "X1") (pin "7") (pinfunction "KL_7") (pintype "passive"))
    )
    (net (code "68") (name "Net-(X1H-KL)") (class "Default")
      (node (ref "D13") (pin "C") (pinfunction "C_C") (pintype "passive"))
      (node (ref "X1") (pin "8") (pinfunction "KL_8") (pintype "passive"))
    )
    (net (code "69") (name "Net-(X1I-KL)") (class "Default")
      (node (ref "D15") (pin "C") (pinfunction "C_C") (pintype "passive"))
      (node (ref "X1") (pin "9") (pinfunction "KL_9") (pintype "passive"))
    )
    (net (code "70") (name "Net-(X2A-KL)") (class "Default")
      (node (ref "ULN1") (pin "10") (pinfunction "10_10") (pintype "bidirectional"))
      (node (ref "X2") (pin "1") (pinfunction "KL_1") (pintype "passive"))
    )
    (net (code "71") (name "Net-(X2B-KL)") (class "Default")
      (node (ref "ULN1") (pin "11") (pinfunction "11_11") (pintype "bidirectional"))
      (node (ref "X2") (pin "2") (pinfunction "KL_2") (pintype "passive"))
    )
    (net (code "72") (name "Net-(X2C-KL)") (class "Default")
      (node (ref "ULN1") (pin "12") (pinfunction "12_12") (pintype "bidirectional"))
      (node (ref "X2") (pin "3") (pinfunction "KL_3") (pintype "passive"))
    )
    (net (code "73") (name "Net-(X2D-KL)") (class "Default")
      (node (ref "ULN1") (pin "13") (pinfunction "13_13") (pintype "bidirectional"))
      (node (ref "X2") (pin "4") (pinfunction "KL_4") (pintype "passive"))
    )
    (net (code "74") (name "Net-(X2E-KL)") (class "Default")
      (node (ref "ULN1") (pin "14") (pinfunction "14_14") (pintype "bidirectional"))
      (node (ref "X2") (pin "5") (pinfunction "KL_5") (pintype "passive"))
    )
    (net (code "75") (name "Net-(X2F-KL)") (class "Default")
      (node (ref "ULN1") (pin "15") (pinfunction "15_15") (pintype "bidirectional"))
      (node (ref "X2") (pin "6") (pinfunction "KL_6") (pintype "passive"))
    )
    (net (code "76") (name "Net-(X2G-KL)") (class "Default")
      (node (ref "ULN1") (pin "16") (pinfunction "16_16") (pintype "bidirectional"))
      (node (ref "X2") (pin "7") (pinfunction "KL_7") (pintype "passive"))
    )
    (net (code "77") (name "Net-(X2H-KL)") (class "Default")
      (node (ref "ULN1") (pin "17") (pinfunction "17_17") (pintype "bidirectional"))
      (node (ref "X2") (pin "8") (pinfunction "KL_8") (pintype "passive"))
    )
    (net (code "78") (name "Net-(X2I-KL)") (class "Default")
      (node (ref "ULN1") (pin "18") (pinfunction "18_18") (pintype "bidirectional"))
      (node (ref "X2") (pin "9") (pinfunction "KL_9") (pintype "passive"))
    )
    (net (code "79") (name "Net-(X4A-K)") (class "Default")
      (node (ref "ULN2") (pin "11") (pinfunction "11_11") (pintype "bidirectional"))
      (node (ref "X4") (pin "1") (pinfunction "K_1") (pintype "passive"))
    )
    (net (code "80") (name "Net-(X4C-K)") (class "Default")
      (node (ref "ULN2") (pin "12") (pinfunction "12_12") (pintype "bidirectional"))
      (node (ref "X4") (pin "3") (pinfunction "K_3") (pintype "passive"))
    )
    (net (code "81") (name "Net-(X4E-K)") (class "Default")
      (node (ref "ULN2") (pin "13") (pinfunction "13_13") (pintype "bidirectional"))
      (node (ref "X4") (pin "5") (pinfunction "K_5") (pintype "passive"))
    )
    (net (code "82") (name "Net-(X4G-K)") (class "Default")
      (node (ref "ULN2") (pin "14") (pinfunction "14_14") (pintype "bidirectional"))
      (node (ref "X4") (pin "7") (pinfunction "K_7") (pintype "passive"))
    )
    (net (code "83") (name "PT100-1") (class "Default")
      (node (ref "C10") (pin "1") (pinfunction "1_1") (pintype "passive"))
      (node (ref "R31") (pin "1") (pinfunction "1_1") (pintype "passive"))
      (node (ref "U$2") (pin "16") (pinfunction "IN0_16") (pintype "input"))
    )
    (net (code "84") (name "PT100-2") (class "Default")
      (node (ref "C11") (pin "1") (pinfunction "1_1") (pintype "passive"))
      (node (ref "R32") (pin "1") (pinfunction "1_1") (pintype "passive"))
      (node (ref "U$2") (pin "15") (pinfunction "IN1_15") (pintype "input"))
    )
    (net (code "85") (name "PT100-3") (class "Default")
      (node (ref "C12") (pin "1") (pinfunction "1_1") (pintype "passive"))
      (node (ref "R33") (pin "1") (pinfunction "1_1") (pintype "passive"))
      (node (ref "U$2") (pin "14") (pinfunction "IN2_14") (pintype "input"))
    )
    (net (code "86") (name "PT100-4") (class "Default")
      (node (ref "C15") (pin "1") (pinfunction "1_1") (pintype "passive"))
      (node (ref "R44") (pin "1") (pinfunction "1_1") (pintype "passive"))
      (node (ref "U$2") (pin "13") (pinfunction "IN3_13") (pintype "input"))
    )
    (net (code "87") (name "PWM1") (class "Default")
      (node (ref "SV1") (pin "4") (pinfunction "4_4") (pintype "passive"))
      (node (ref "ULN2") (pin "8") (pinfunction "8_8") (pintype "bidirectional"))
    )
    (net (code "88") (name "PWM2") (class "Default")
      (node (ref "SV1") (pin "2") (pinfunction "2_2") (pintype "passive"))
      (node (ref "ULN2") (pin "7") (pinfunction "7_7") (pintype "bidirectional"))
    )
    (net (code "89") (name "PWM3") (class "Default")
      (node (ref "SV1") (pin "1") (pinfunction "1_1") (pintype "passive"))
      (node (ref "ULN2") (pin "6") (pinfunction "6_6") (pintype "bidirectional"))
    )
    (net (code "90") (name "PWM4") (class "Default")
      (node (ref "SV1") (pin "3") (pinfunction "3_3") (pintype "passive"))
      (node (ref "ULN2") (pin "5") (pinfunction "5_5") (pintype "bidirectional"))
    )
    (net (code "91") (name "SCL") (class "Default")
      (node (ref "IC5") (pin "12") (pinfunction "SCL_12") (pintype "input"))
      (node (ref "SV1") (pin "7") (pinfunction "7_7") (pintype "passive"))
      (node (ref "U$2") (pin "3") (pinfunction "SCL_3") (pintype "input"))
    )
    (net (code "92") (name "SDA") (class "Default")
      (node (ref "IC5") (pin "13") (pinfunction "SDA_13") (pintype "bidirectional"))
      (node (ref "SV1") (pin "8") (pinfunction "8_8") (pintype "passive"))
      (node (ref "U$2") (pin "2") (pinfunction "SDA_2") (pintype "bidirectional"))
    )
    (net (code "93") (name "VCC") (class "Default")
      (node (ref "C1") (pin "1") (pinfunction "1_1") (pintype "passive"))
      (node (ref "C16") (pin "2") (pinfunction "2_2") (pintype "passive"))
      (node (ref "C17") (pin "1") (pinfunction "1_1") (pintype "passive"))
      (node (ref "C19") (pin "1") (pinfunction "1_1") (pintype "passive"))
      (node (ref "C2") (pin "1") (pinfunction "1_1") (pintype "passive"))
      (node (ref "IC2") (pin "4") (pinfunction "V+_4") (pintype "power_in"))
      (node (ref "IC5") (pin "9") (pinfunction "VDD_9") (pintype "power_in"))
      (node (ref "R47") (pin "2") (pinfunction "2_2") (pintype "passive"))
      (node (ref "R48") (pin "2") (pinfunction "2_2") (pintype "passive"))
      (node (ref "SV1") (pin "9") (pinfunction "9_9") (pintype "passive"))
      (node (ref "U$1") (pin "3") (pinfunction "EN_3") (pintype "bidirectional"))
      (node (ref "U$1") (pin "4") (pinfunction "VIN_4") (pintype "bidirectional"))
      (node (ref "U$2") (pin "5") (pinfunction "VCC_5") (pintype "power_in"))
      (node (ref "ULN2") (pin "10") (pinfunction "10_10") (pintype "bidirectional"))
      (node (ref "X3") (pin "2") (pinfunction "K_2") (pintype "passive"))
      (node (ref "X4") (pin "2") (pinfunction "K_2") (pintype "passive"))
      (node (ref "X4") (pin "4") (pinfunction "K_4") (pintype "passive"))
      (node (ref "X4") (pin "6") (pinfunction "K_6") (pintype "passive"))
      (node (ref "X4") (pin "8") (pinfunction "K_8") (pintype "passive"))
    )
    (net (code "94") (name "VREF") (class "Default")
      (node (ref "C9") (pin "1") (pinfunction "1_1") (pintype "passive"))
      (node (ref "IC1") (pin "5") (pinfunction "IN+_5") (pintype "input"))
      (node (ref "IC2") (pin "5") (pinfunction "IN+_5") (pintype "input"))
      (node (ref "IC3") (pin "5") (pinfunction "IN+_5") (pintype "input"))
      (node (ref "IC4") (pin "5") (pinfunction "IN+_5") (pintype "input"))
      (node (ref "U$1") (pin "5") (pinfunction "VOUT_5") (pintype "bidirectional"))
    )
    (net (code "95") (name "unconnected-(IC5-INTB-Pad19)") (class "Default")
      (node (ref "IC5") (pin "19") (pinfunction "INTB_19") (pintype "output"))
    )
    (net (code "96") (name "unconnected-(IC5-~{RESET}-Pad18)") (class "Default")
      (node (ref "IC5") (pin "18") (pinfunction "~{RESET}_18") (pintype "input"))
    )
    (net (code "97") (name "unconnected-(SV1-Pad6)") (class "Default")
      (node (ref "SV1") (pin "6") (pinfunction "6_6") (pintype "passive"))
    )
    (net (code "98") (name "unconnected-(U$2-IN4-Pad12)") (class "Default")
      (node (ref "U$2") (pin "12") (pinfunction "IN4_12") (pintype "input"))
    )
    (net (code "99") (name "unconnected-(U$2-IN5-Pad11)") (class "Default")
      (node (ref "U$2") (pin "11") (pinfunction "IN5_11") (pintype "input"))
    )
    (net (code "100") (name "unconnected-(U$2-IN6-Pad10)") (class "Default")
      (node (ref "U$2") (pin "10") (pinfunction "IN6_10") (pintype "input"))
    )
    (net (code "101") (name "unconnected-(U$2-IN7-Pad9)") (class "Default")
      (node (ref "U$2") (pin "9") (pinfunction "IN7_9") (pintype "input"))
    )
    (net (code "102") (name "unconnected-(U$2-{slash}INT-Pad6)") (class "Default")
      (node (ref "U$2") (pin "6") (pinfunction "/INT_6") (pintype "output"))
    )
    (net (code "103") (name "unconnected-(ULN2-Pad1)") (class "Default")
      (node (ref "ULN2") (pin "1") (pinfunction "1_1") (pintype "bidirectional"))
    )
    (net (code "104") (name "unconnected-(ULN2-Pad2)") (class "Default")
      (node (ref "ULN2") (pin "2") (pinfunction "2_2") (pintype "bidirectional"))
    )
    (net (code "105") (name "unconnected-(ULN2-Pad3)") (class "Default")
      (node (ref "ULN2") (pin "3") (pinfunction "3_3") (pintype "bidirectional"))
    )
    (net (code "106") (name "unconnected-(ULN2-Pad4)") (class "Default")
      (node (ref "ULN2") (pin "4") (pinfunction "4_4") (pintype "bidirectional"))
    )
    (net (code "107") (name "unconnected-(ULN2-Pad15)") (class "Default")
      (node (ref "ULN2") (pin "15") (pinfunction "15_15") (pintype "bidirectional"))
    )
    (net (code "108") (name "unconnected-(ULN2-Pad16)") (class "Default")
      (node (ref "ULN2") (pin "16") (pinfunction "16_16") (pintype "bidirectional"))
    )
    (net (code "109") (name "unconnected-(ULN2-Pad17)") (class "Default")
      (node (ref "ULN2") (pin "17") (pinfunction "17_17") (pintype "bidirectional"))
    )
    (net (code "110") (name "unconnected-(ULN2-Pad18)") (class "Default")
      (node (ref "ULN2") (pin "18") (pinfunction "18_18") (pintype "bidirectional"))
    )
    (net (code "111") (name "unconnected-(X3C-K-Pad3)") (class "Default")
      (node (ref "X3") (pin "3") (pinfunction "K_3") (pintype "passive"))
    )
    (net (code "112") (name "unconnected-(X3D-K-Pad4)") (class "Default")
      (node (ref "X3") (pin "4") (pinfunction "K_4") (pintype "passive"))
    )
  )
)
